# SheetMain.net
KiCad netlist of a schematic drawn in Altium Designer
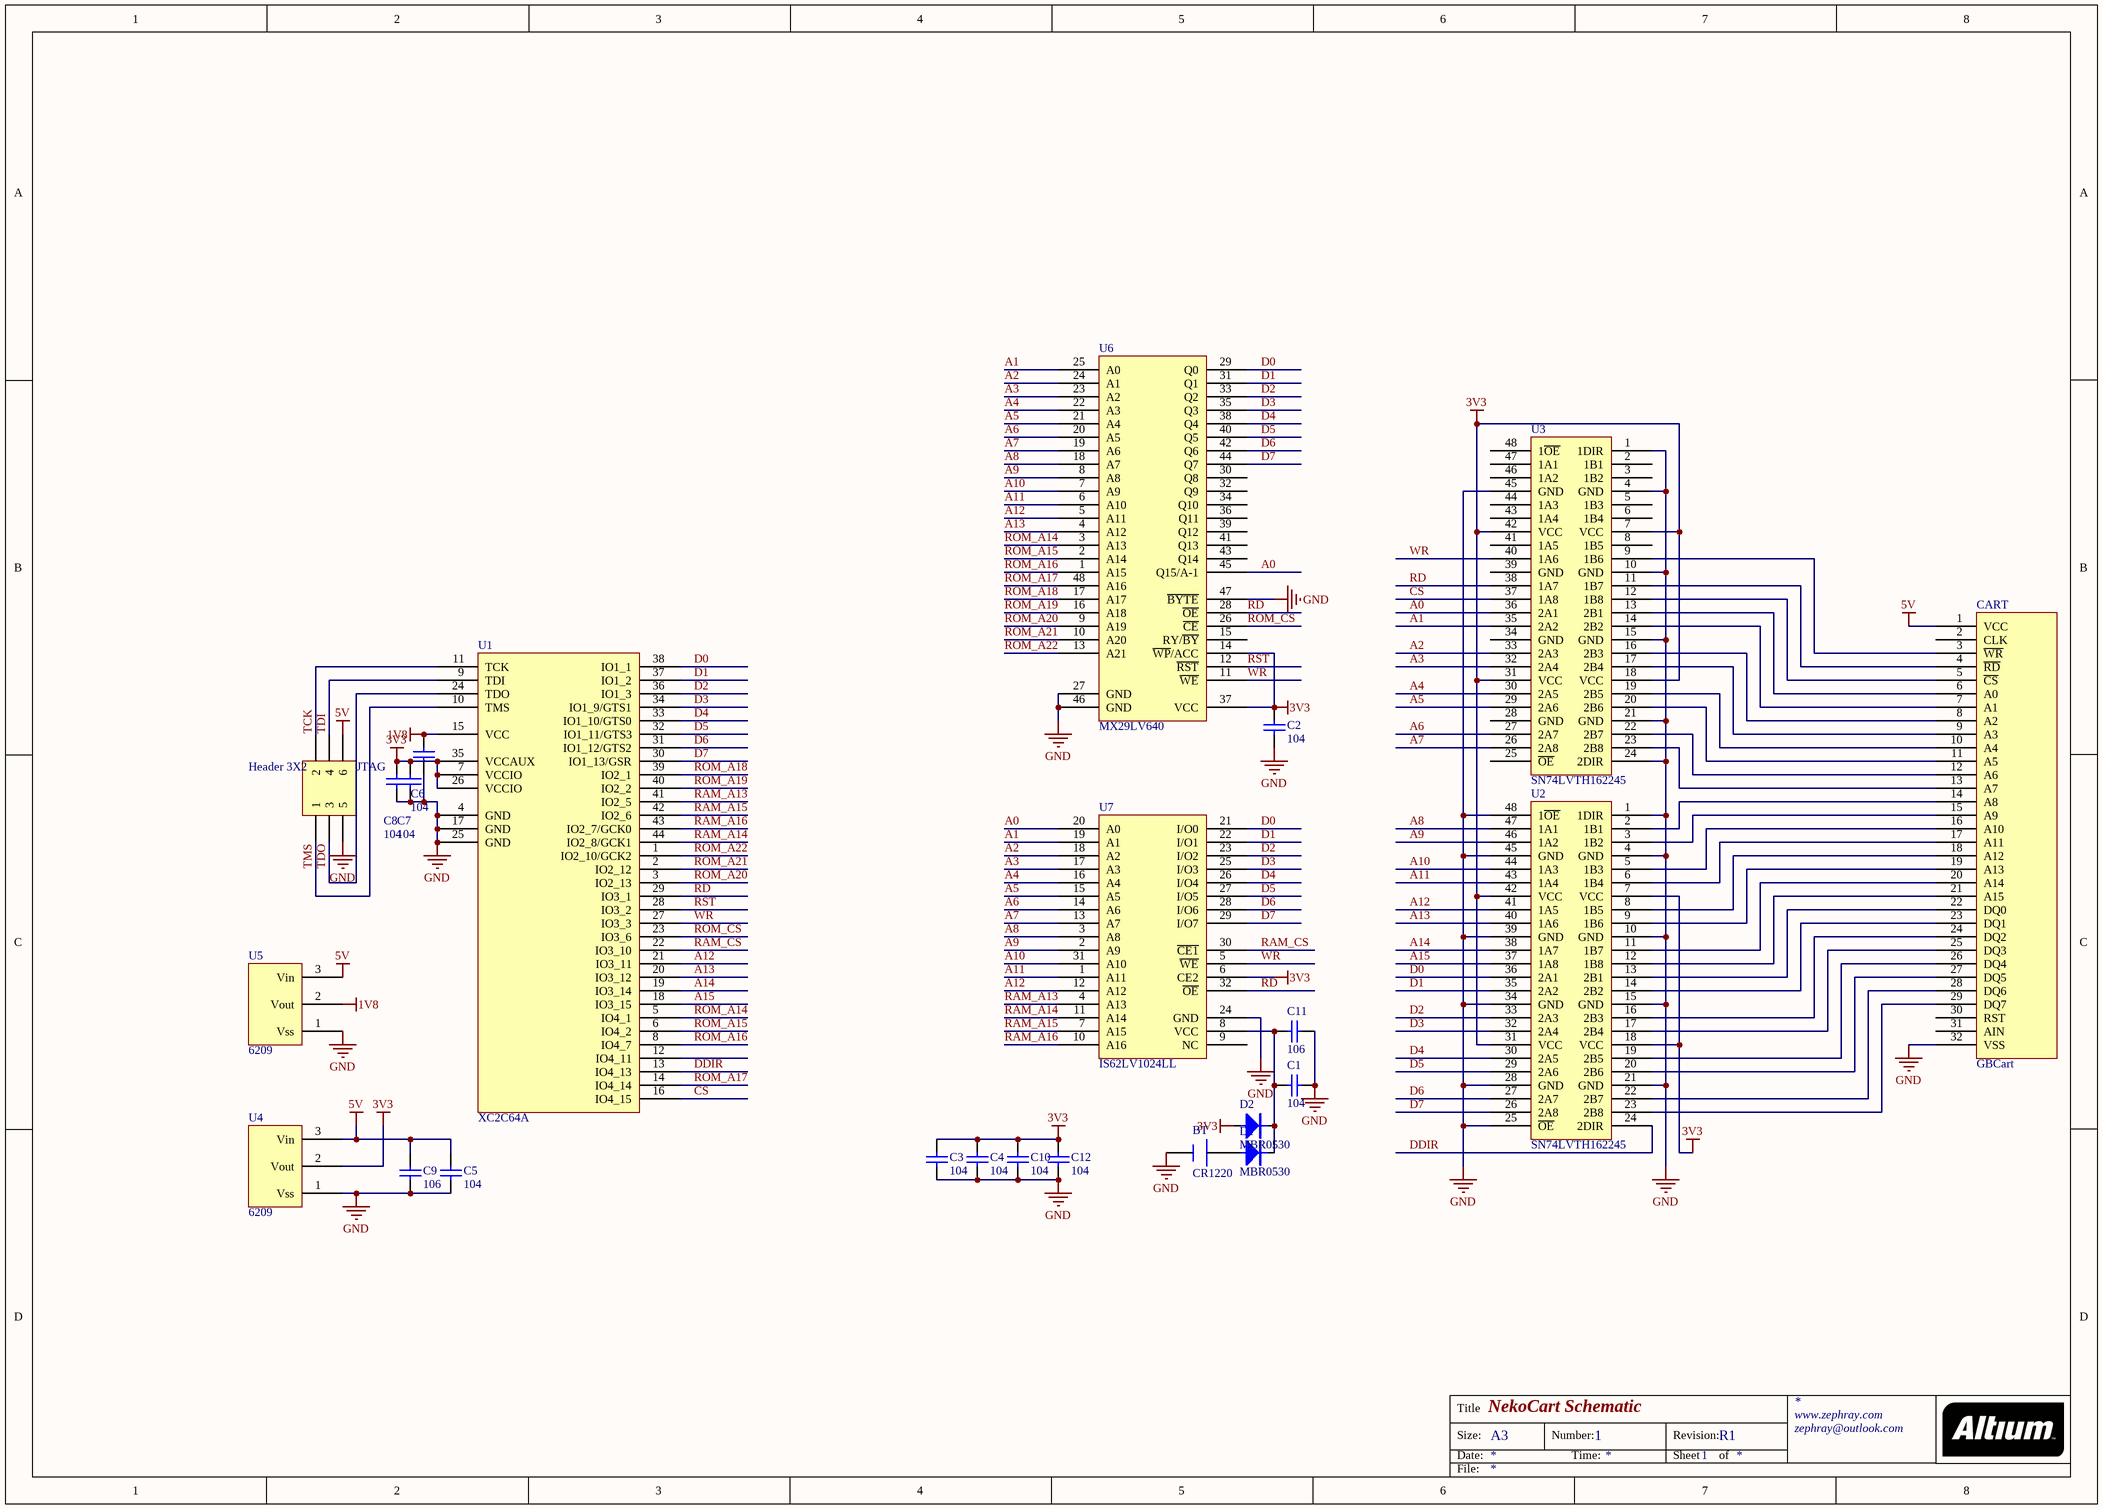
[diagram p0: SheetMain.SchDoc]

(export (version "E")
  (design (tool "Eeschema 10.0.6"))
  (components
    (comp (ref "BT")
      (value "CR1220")
      (footprint "CR1220")
      (fields (field (name "PUBLISHER") "Altium Limited"))
      (libsource (lib "Schlib1") (part "CR1220"))
    )
    (comp (ref "C1")
      (value "104")
      (footprint "1608[0603]")
      (description "Capacitor (Semiconductor SIM Model)")
      (fields (field (name "PUBLISHER") "Altium Limited"))
      (libsource (lib "Miscellaneous Devices") (part "Cap Semi"))
    )
    (comp (ref "C2")
      (value "104")
      (footprint "1608[0603]")
      (description "Capacitor (Semiconductor SIM Model)")
      (fields (field (name "PUBLISHER") "Altium Limited"))
      (libsource (lib "Miscellaneous Devices") (part "Cap Semi"))
    )
    (comp (ref "C3")
      (value "104")
      (footprint "1608[0603]")
      (description "Capacitor (Semiconductor SIM Model)")
      (fields (field (name "PUBLISHER") "Altium Limited"))
      (libsource (lib "Miscellaneous Devices") (part "Cap Semi"))
    )
    (comp (ref "C4")
      (value "104")
      (footprint "1608[0603]")
      (description "Capacitor (Semiconductor SIM Model)")
      (fields (field (name "PUBLISHER") "Altium Limited"))
      (libsource (lib "Miscellaneous Devices") (part "Cap Semi"))
    )
    (comp (ref "C5")
      (value "104")
      (footprint "1608[0603]")
      (description "Capacitor (Semiconductor SIM Model)")
      (fields (field (name "PUBLISHER") "Altium Limited"))
      (libsource (lib "Miscellaneous Devices") (part "Cap Semi"))
    )
    (comp (ref "C6")
      (value "104")
      (footprint "1608[0603]")
      (description "Capacitor (Semiconductor SIM Model)")
      (fields (field (name "PUBLISHER") "Altium Limited"))
      (libsource (lib "Miscellaneous Devices") (part "Cap Semi"))
    )
    (comp (ref "C7")
      (value "104")
      (footprint "1608[0603]")
      (description "Capacitor (Semiconductor SIM Model)")
      (fields (field (name "PUBLISHER") "Altium Limited"))
      (libsource (lib "Miscellaneous Devices") (part "Cap Semi"))
    )
    (comp (ref "C8")
      (value "104")
      (footprint "1608[0603]")
      (description "Capacitor (Semiconductor SIM Model)")
      (fields (field (name "PUBLISHER") "Altium Limited"))
      (libsource (lib "Miscellaneous Devices") (part "Cap Semi"))
    )
    (comp (ref "C9")
      (value "106")
      (footprint "C0805")
      (description "Capacitor (Semiconductor SIM Model)")
      (fields (field (name "PUBLISHER") "Altium Limited"))
      (libsource (lib "Miscellaneous Devices") (part "Cap Semi"))
    )
    (comp (ref "C10")
      (value "104")
      (footprint "1608[0603]")
      (description "Capacitor (Semiconductor SIM Model)")
      (fields (field (name "PUBLISHER") "Altium Limited"))
      (libsource (lib "Miscellaneous Devices") (part "Cap Semi"))
    )
    (comp (ref "C11")
      (value "106")
      (footprint "C0805")
      (description "Capacitor (Semiconductor SIM Model)")
      (fields (field (name "PUBLISHER") "Altium Limited"))
      (libsource (lib "Miscellaneous Devices") (part "Cap Semi"))
    )
    (comp (ref "C12")
      (value "104")
      (footprint "1608[0603]")
      (description "Capacitor (Semiconductor SIM Model)")
      (fields (field (name "PUBLISHER") "Altium Limited"))
      (libsource (lib "Miscellaneous Devices") (part "Cap Semi"))
    )
    (comp (ref "CART") (value "GBCart") (footprint "GB_CART") (libsource (lib "Schlib1") (part "GBCart")))
    (comp (ref "D1") (value "MBR0530") (footprint "0805D") (libsource (lib "Schlib1") (part "1N4148")))
    (comp (ref "D2") (value "MBR0530") (footprint "0805D") (libsource (lib "Schlib1") (part "1N4148")))
    (comp (ref "JTAG")
      (value "Header 3X2")
      (footprint "HDR2X3")
      (description "Header, 3-Pin, Dual row")
      (fields (field (name "PUBLISHER") "Altium Limited"))
      (libsource (lib "Miscellaneous Connectors") (part "Header 3X2"))
    )
    (comp (ref "U1") (value "XC2C64A") (footprint "44A_L") (libsource (lib "Schlib1") (part "XC2C64A")))
    (comp (ref "U2")
      (value "SN74LVTH162245")
      (footprint "TSOP48")
      (libsource (lib "Schlib1") (part "SN74LVTH162245"))
    )
    (comp (ref "U3")
      (value "SN74LVTH162245")
      (footprint "TSOP48")
      (libsource (lib "Schlib1") (part "SN74LVTH162245"))
    )
    (comp (ref "U4") (value "6209") (footprint "SOT-23") (libsource (lib "Schlib1") (part "6209")))
    (comp (ref "U5") (value "6209") (footprint "SOT-23") (libsource (lib "Schlib1") (part "6209")))
    (comp (ref "U6") (value "MX29LV640") (footprint "TSOP48L") (libsource (lib "Schlib1") (part "MX29LV640")))
    (comp (ref "U7")
      (value "IS62LV1024LL")
      (footprint "TSOP32")
      (libsource (lib "Schlib1") (part "IS62LV1024LL"))
    )
  )
  (nets
    (net (code "1") (name "/A0") (class "Default")
      (node (ref "U3") (pin "36") (pinfunction "2A1_36") (pintype "passive"))
      (node (ref "U6") (pin "45") (pinfunction "Q15/A-1_45") (pintype "passive"))
      (node (ref "U7") (pin "20") (pinfunction "A0_20") (pintype "passive"))
    )
    (net (code "2") (name "/A1") (class "Default")
      (node (ref "U3") (pin "35") (pinfunction "2A2_35") (pintype "passive"))
      (node (ref "U6") (pin "25") (pinfunction "A0_25") (pintype "passive"))
      (node (ref "U7") (pin "19") (pinfunction "A1_19") (pintype "passive"))
    )
    (net (code "3") (name "/A2") (class "Default")
      (node (ref "U3") (pin "33") (pinfunction "2A3_33") (pintype "passive"))
      (node (ref "U6") (pin "24") (pinfunction "A1_24") (pintype "passive"))
      (node (ref "U7") (pin "18") (pinfunction "A2_18") (pintype "passive"))
    )
    (net (code "4") (name "/A3") (class "Default")
      (node (ref "U3") (pin "32") (pinfunction "2A4_32") (pintype "passive"))
      (node (ref "U6") (pin "23") (pinfunction "A2_23") (pintype "passive"))
      (node (ref "U7") (pin "17") (pinfunction "A3_17") (pintype "passive"))
    )
    (net (code "5") (name "/A4") (class "Default")
      (node (ref "U3") (pin "30") (pinfunction "2A5_30") (pintype "passive"))
      (node (ref "U6") (pin "22") (pinfunction "A3_22") (pintype "passive"))
      (node (ref "U7") (pin "16") (pinfunction "A4_16") (pintype "passive"))
    )
    (net (code "6") (name "/A5") (class "Default")
      (node (ref "U3") (pin "29") (pinfunction "2A6_29") (pintype "passive"))
      (node (ref "U6") (pin "21") (pinfunction "A4_21") (pintype "passive"))
      (node (ref "U7") (pin "15") (pinfunction "A5_15") (pintype "passive"))
    )
    (net (code "7") (name "/A6") (class "Default")
      (node (ref "U3") (pin "27") (pinfunction "2A7_27") (pintype "passive"))
      (node (ref "U6") (pin "20") (pinfunction "A5_20") (pintype "passive"))
      (node (ref "U7") (pin "14") (pinfunction "A6_14") (pintype "passive"))
    )
    (net (code "8") (name "/A7") (class "Default")
      (node (ref "U3") (pin "26") (pinfunction "2A8_26") (pintype "passive"))
      (node (ref "U6") (pin "19") (pinfunction "A6_19") (pintype "passive"))
      (node (ref "U7") (pin "13") (pinfunction "A7_13") (pintype "passive"))
    )
    (net (code "9") (name "/A8") (class "Default")
      (node (ref "U2") (pin "47") (pinfunction "1A1_47") (pintype "passive"))
      (node (ref "U6") (pin "18") (pinfunction "A7_18") (pintype "passive"))
      (node (ref "U7") (pin "3") (pinfunction "A8_3") (pintype "passive"))
    )
    (net (code "10") (name "/A9") (class "Default")
      (node (ref "U2") (pin "46") (pinfunction "1A2_46") (pintype "passive"))
      (node (ref "U6") (pin "8") (pinfunction "A8_8") (pintype "passive"))
      (node (ref "U7") (pin "2") (pinfunction "A9_2") (pintype "passive"))
    )
    (net (code "11") (name "/A10") (class "Default")
      (node (ref "U2") (pin "44") (pinfunction "1A3_44") (pintype "passive"))
      (node (ref "U6") (pin "7") (pinfunction "A9_7") (pintype "passive"))
      (node (ref "U7") (pin "31") (pinfunction "A10_31") (pintype "passive"))
    )
    (net (code "12") (name "/A11") (class "Default")
      (node (ref "U2") (pin "43") (pinfunction "1A4_43") (pintype "passive"))
      (node (ref "U6") (pin "6") (pinfunction "A10_6") (pintype "passive"))
      (node (ref "U7") (pin "1") (pinfunction "A11_1") (pintype "passive"))
    )
    (net (code "13") (name "/A12") (class "Default")
      (node (ref "U1") (pin "21") (pinfunction "IO3_11_21") (pintype "passive"))
      (node (ref "U2") (pin "41") (pinfunction "1A5_41") (pintype "passive"))
      (node (ref "U6") (pin "5") (pinfunction "A11_5") (pintype "passive"))
      (node (ref "U7") (pin "12") (pinfunction "A12_12") (pintype "passive"))
    )
    (net (code "14") (name "/A13") (class "Default")
      (node (ref "U1") (pin "20") (pinfunction "IO3_12_20") (pintype "passive"))
      (node (ref "U2") (pin "40") (pinfunction "1A6_40") (pintype "passive"))
      (node (ref "U6") (pin "4") (pinfunction "A12_4") (pintype "passive"))
    )
    (net (code "15") (name "/A14") (class "Default")
      (node (ref "U1") (pin "19") (pinfunction "IO3_14_19") (pintype "passive"))
      (node (ref "U2") (pin "38") (pinfunction "1A7_38") (pintype "passive"))
    )
    (net (code "16") (name "/A15") (class "Default")
      (node (ref "U1") (pin "18") (pinfunction "IO3_15_18") (pintype "passive"))
      (node (ref "U2") (pin "37") (pinfunction "1A8_37") (pintype "passive"))
    )
    (net (code "17") (name "/CS") (class "Default")
      (node (ref "U1") (pin "16") (pinfunction "IO4_15_16") (pintype "passive"))
      (node (ref "U3") (pin "37") (pinfunction "1A8_37") (pintype "passive"))
    )
    (net (code "18") (name "/D0") (class "Default")
      (node (ref "U1") (pin "38") (pinfunction "IO1_1_38") (pintype "passive"))
      (node (ref "U2") (pin "36") (pinfunction "2A1_36") (pintype "passive"))
      (node (ref "U6") (pin "29") (pinfunction "Q0_29") (pintype "passive"))
      (node (ref "U7") (pin "21") (pinfunction "I/O0_21") (pintype "passive"))
    )
    (net (code "19") (name "/D1") (class "Default")
      (node (ref "U1") (pin "37") (pinfunction "IO1_2_37") (pintype "passive"))
      (node (ref "U2") (pin "35") (pinfunction "2A2_35") (pintype "passive"))
      (node (ref "U6") (pin "31") (pinfunction "Q1_31") (pintype "passive"))
      (node (ref "U7") (pin "22") (pinfunction "I/O1_22") (pintype "passive"))
    )
    (net (code "20") (name "/D2") (class "Default")
      (node (ref "U1") (pin "36") (pinfunction "IO1_3_36") (pintype "passive"))
      (node (ref "U2") (pin "33") (pinfunction "2A3_33") (pintype "passive"))
      (node (ref "U6") (pin "33") (pinfunction "Q2_33") (pintype "passive"))
      (node (ref "U7") (pin "23") (pinfunction "I/O2_23") (pintype "passive"))
    )
    (net (code "21") (name "/D3") (class "Default")
      (node (ref "U1") (pin "34") (pinfunction "IO1_9/GTS1_34") (pintype "passive"))
      (node (ref "U2") (pin "32") (pinfunction "2A4_32") (pintype "passive"))
      (node (ref "U6") (pin "35") (pinfunction "Q3_35") (pintype "passive"))
      (node (ref "U7") (pin "25") (pinfunction "I/O3_25") (pintype "passive"))
    )
    (net (code "22") (name "/D4") (class "Default")
      (node (ref "U1") (pin "33") (pinfunction "IO1_10/GTS0_33") (pintype "passive"))
      (node (ref "U2") (pin "30") (pinfunction "2A5_30") (pintype "passive"))
      (node (ref "U6") (pin "38") (pinfunction "Q4_38") (pintype "passive"))
      (node (ref "U7") (pin "26") (pinfunction "I/O4_26") (pintype "passive"))
    )
    (net (code "23") (name "/D5") (class "Default")
      (node (ref "U1") (pin "32") (pinfunction "IO1_11/GTS3_32") (pintype "passive"))
      (node (ref "U2") (pin "29") (pinfunction "2A6_29") (pintype "passive"))
      (node (ref "U6") (pin "40") (pinfunction "Q5_40") (pintype "passive"))
      (node (ref "U7") (pin "27") (pinfunction "I/O5_27") (pintype "passive"))
    )
    (net (code "24") (name "/D6") (class "Default")
      (node (ref "U1") (pin "31") (pinfunction "IO1_12/GTS2_31") (pintype "passive"))
      (node (ref "U2") (pin "27") (pinfunction "2A7_27") (pintype "passive"))
      (node (ref "U6") (pin "42") (pinfunction "Q6_42") (pintype "passive"))
      (node (ref "U7") (pin "28") (pinfunction "I/O6_28") (pintype "passive"))
    )
    (net (code "25") (name "/D7") (class "Default")
      (node (ref "U1") (pin "30") (pinfunction "IO1_13/GSR_30") (pintype "passive"))
      (node (ref "U2") (pin "26") (pinfunction "2A8_26") (pintype "passive"))
      (node (ref "U6") (pin "44") (pinfunction "Q7_44") (pintype "passive"))
      (node (ref "U7") (pin "29") (pinfunction "I/O7_29") (pintype "passive"))
    )
    (net (code "26") (name "/DDIR") (class "Default")
      (node (ref "U1") (pin "13") (pinfunction "IO4_13_13") (pintype "passive"))
      (node (ref "U2") (pin "24") (pinfunction "2DIR_24") (pintype "passive"))
    )
    (net (code "27") (name "/RAM_A13") (class "Default")
      (node (ref "U1") (pin "41") (pinfunction "IO2_5_41") (pintype "passive"))
      (node (ref "U7") (pin "4") (pinfunction "A13_4") (pintype "passive"))
    )
    (net (code "28") (name "/RAM_A14") (class "Default")
      (node (ref "U1") (pin "44") (pinfunction "IO2_8/GCK1_44") (pintype "passive"))
      (node (ref "U7") (pin "11") (pinfunction "A14_11") (pintype "passive"))
    )
    (net (code "29") (name "/RAM_A15") (class "Default")
      (node (ref "U1") (pin "42") (pinfunction "IO2_6_42") (pintype "passive"))
      (node (ref "U7") (pin "7") (pinfunction "A15_7") (pintype "passive"))
    )
    (net (code "30") (name "/RAM_A16") (class "Default")
      (node (ref "U1") (pin "43") (pinfunction "IO2_7/GCK0_43") (pintype "passive"))
      (node (ref "U7") (pin "10") (pinfunction "A16_10") (pintype "passive"))
    )
    (net (code "31") (name "/RAM_CS") (class "Default")
      (node (ref "U1") (pin "22") (pinfunction "IO3_10_22") (pintype "passive"))
      (node (ref "U7") (pin "30") (pinfunction "~{CE1}_30") (pintype "passive"))
    )
    (net (code "32") (name "/RD") (class "Default")
      (node (ref "U1") (pin "29") (pinfunction "IO3_1_29") (pintype "passive"))
      (node (ref "U3") (pin "38") (pinfunction "1A7_38") (pintype "passive"))
      (node (ref "U6") (pin "28") (pinfunction "~{OE}_28") (pintype "passive"))
      (node (ref "U7") (pin "32") (pinfunction "~{OE}_32") (pintype "passive"))
    )
    (net (code "33") (name "/ROM_A14") (class "Default")
      (node (ref "U1") (pin "5") (pinfunction "IO4_1_5") (pintype "passive"))
      (node (ref "U6") (pin "3") (pinfunction "A13_3") (pintype "passive"))
    )
    (net (code "34") (name "/ROM_A15") (class "Default")
      (node (ref "U1") (pin "6") (pinfunction "IO4_2_6") (pintype "passive"))
      (node (ref "U6") (pin "2") (pinfunction "A14_2") (pintype "passive"))
    )
    (net (code "35") (name "/ROM_A16") (class "Default")
      (node (ref "U1") (pin "8") (pinfunction "IO4_7_8") (pintype "passive"))
      (node (ref "U6") (pin "1") (pinfunction "A15_1") (pintype "passive"))
    )
    (net (code "36") (name "/ROM_A17") (class "Default")
      (node (ref "U1") (pin "14") (pinfunction "IO4_14_14") (pintype "passive"))
      (node (ref "U6") (pin "48") (pinfunction "A16_48") (pintype "passive"))
    )
    (net (code "37") (name "/ROM_A18") (class "Default")
      (node (ref "U1") (pin "39") (pinfunction "IO2_1_39") (pintype "passive"))
      (node (ref "U6") (pin "17") (pinfunction "A17_17") (pintype "passive"))
    )
    (net (code "38") (name "/ROM_A19") (class "Default")
      (node (ref "U1") (pin "40") (pinfunction "IO2_2_40") (pintype "passive"))
      (node (ref "U6") (pin "16") (pinfunction "A18_16") (pintype "passive"))
    )
    (net (code "39") (name "/ROM_A20") (class "Default")
      (node (ref "U1") (pin "3") (pinfunction "IO2_13_3") (pintype "passive"))
      (node (ref "U6") (pin "9") (pinfunction "A19_9") (pintype "passive"))
    )
    (net (code "40") (name "/ROM_A21") (class "Default")
      (node (ref "U1") (pin "2") (pinfunction "IO2_12_2") (pintype "passive"))
      (node (ref "U6") (pin "10") (pinfunction "A20_10") (pintype "passive"))
    )
    (net (code "41") (name "/ROM_A22") (class "Default")
      (node (ref "U1") (pin "1") (pinfunction "IO2_10/GCK2_1") (pintype "passive"))
      (node (ref "U6") (pin "13") (pinfunction "A21_13") (pintype "passive"))
    )
    (net (code "42") (name "/ROM_CS") (class "Default")
      (node (ref "U1") (pin "23") (pinfunction "IO3_6_23") (pintype "passive"))
      (node (ref "U6") (pin "26") (pinfunction "~{CE}_26") (pintype "passive"))
    )
    (net (code "43") (name "/RST") (class "Default")
      (node (ref "U1") (pin "28") (pinfunction "IO3_2_28") (pintype "passive"))
      (node (ref "U6") (pin "12") (pinfunction "~{RST}_12") (pintype "passive"))
    )
    (net (code "44") (name "/TCK") (class "Default")
      (node (ref "JTAG") (pin "2") (pinfunction "2_2") (pintype "passive"))
      (node (ref "U1") (pin "11") (pinfunction "TCK_11") (pintype "passive"))
    )
    (net (code "45") (name "/TDI") (class "Default")
      (node (ref "JTAG") (pin "4") (pinfunction "4_4") (pintype "passive"))
      (node (ref "U1") (pin "9") (pinfunction "TDI_9") (pintype "passive"))
    )
    (net (code "46") (name "/TDO") (class "Default")
      (node (ref "JTAG") (pin "3") (pinfunction "3_3") (pintype "passive"))
      (node (ref "U1") (pin "24") (pinfunction "TDO_24") (pintype "passive"))
    )
    (net (code "47") (name "/TMS") (class "Default")
      (node (ref "JTAG") (pin "1") (pinfunction "1_1") (pintype "passive"))
      (node (ref "U1") (pin "10") (pinfunction "TMS_10") (pintype "passive"))
    )
    (net (code "48") (name "/WR") (class "Default")
      (node (ref "U1") (pin "27") (pinfunction "IO3_3_27") (pintype "passive"))
      (node (ref "U3") (pin "40") (pinfunction "1A6_40") (pintype "passive"))
      (node (ref "U6") (pin "11") (pinfunction "~{WE}_11") (pintype "passive"))
      (node (ref "U7") (pin "5") (pinfunction "~{WE}_5") (pintype "passive"))
    )
    (net (code "49") (name "1V8") (class "Default")
      (node (ref "C6") (pin "2") (pinfunction "2_2") (pintype "passive"))
      (node (ref "U1") (pin "15") (pinfunction "VCC_15") (pintype "passive"))
      (node (ref "U5") (pin "2") (pinfunction "Vout_2") (pintype "passive"))
    )
    (net (code "50") (name "3V3") (class "Default")
      (node (ref "C10") (pin "1") (pinfunction "1_1") (pintype "passive"))
      (node (ref "C12") (pin "2") (pinfunction "2_2") (pintype "passive"))
      (node (ref "C2") (pin "2") (pinfunction "2_2") (pintype "passive"))
      (node (ref "C3") (pin "2") (pinfunction "2_2") (pintype "passive"))
      (node (ref "C4") (pin "2") (pinfunction "2_2") (pintype "passive"))
      (node (ref "C7") (pin "2") (pinfunction "2_2") (pintype "passive"))
      (node (ref "C8") (pin "2") (pinfunction "2_2") (pintype "passive"))
      (node (ref "D2") (pin "A") (pinfunction "1_A") (pintype "passive"))
      (node (ref "U1") (pin "26") (pinfunction "VCCIO_26") (pintype "passive"))
      (node (ref "U1") (pin "35") (pinfunction "VCCAUX_35") (pintype "passive"))
      (node (ref "U1") (pin "7") (pinfunction "VCCIO_7") (pintype "passive"))
      (node (ref "U2") (pin "18") (pinfunction "VCC_18") (pintype "passive"))
      (node (ref "U2") (pin "31") (pinfunction "VCC_31") (pintype "passive"))
      (node (ref "U2") (pin "42") (pinfunction "VCC_42") (pintype "passive"))
      (node (ref "U2") (pin "7") (pinfunction "VCC_7") (pintype "passive"))
      (node (ref "U3") (pin "18") (pinfunction "VCC_18") (pintype "passive"))
      (node (ref "U3") (pin "31") (pinfunction "VCC_31") (pintype "passive"))
      (node (ref "U3") (pin "42") (pinfunction "VCC_42") (pintype "passive"))
      (node (ref "U3") (pin "7") (pinfunction "VCC_7") (pintype "passive"))
      (node (ref "U4") (pin "2") (pinfunction "Vout_2") (pintype "passive"))
      (node (ref "U6") (pin "14") (pinfunction "~{WP}/ACC_14") (pintype "passive"))
      (node (ref "U6") (pin "37") (pinfunction "VCC_37") (pintype "passive"))
      (node (ref "U7") (pin "6") (pinfunction "CE2_6") (pintype "passive"))
    )
    (net (code "51") (name "5V") (class "Default")
      (node (ref "C5") (pin "2") (pinfunction "2_2") (pintype "passive"))
      (node (ref "C9") (pin "2") (pinfunction "2_2") (pintype "passive"))
      (node (ref "CART") (pin "1") (pinfunction "VCC_1") (pintype "passive"))
      (node (ref "JTAG") (pin "6") (pinfunction "6_6") (pintype "passive"))
      (node (ref "U4") (pin "3") (pinfunction "Vin_3") (pintype "passive"))
      (node (ref "U5") (pin "3") (pinfunction "Vin_3") (pintype "passive"))
    )
    (net (code "52") (name "GND") (class "Default")
      (node (ref "BT") (pin "2") (pinfunction "-_2") (pintype "passive"))
      (node (ref "C1") (pin "1") (pinfunction "1_1") (pintype "passive"))
      (node (ref "C10") (pin "2") (pinfunction "2_2") (pintype "passive"))
      (node (ref "C11") (pin "1") (pinfunction "1_1") (pintype "passive"))
      (node (ref "C12") (pin "1") (pinfunction "1_1") (pintype "passive"))
      (node (ref "C2") (pin "1") (pinfunction "1_1") (pintype "passive"))
      (node (ref "C3") (pin "1") (pinfunction "1_1") (pintype "passive"))
      (node (ref "C4") (pin "1") (pinfunction "1_1") (pintype "passive"))
      (node (ref "C5") (pin "1") (pinfunction "1_1") (pintype "passive"))
      (node (ref "C6") (pin "1") (pinfunction "1_1") (pintype "passive"))
      (node (ref "C7") (pin "1") (pinfunction "1_1") (pintype "passive"))
      (node (ref "C8") (pin "1") (pinfunction "1_1") (pintype "passive"))
      (node (ref "C9") (pin "1") (pinfunction "1_1") (pintype "passive"))
      (node (ref "CART") (pin "32") (pinfunction "VSS_32") (pintype "passive"))
      (node (ref "JTAG") (pin "5") (pinfunction "5_5") (pintype "passive"))
      (node (ref "U1") (pin "17") (pinfunction "GND_17") (pintype "passive"))
      (node (ref "U1") (pin "25") (pinfunction "GND_25") (pintype "passive"))
      (node (ref "U1") (pin "4") (pinfunction "GND_4") (pintype "passive"))
      (node (ref "U2") (pin "1") (pinfunction "1DIR_1") (pintype "passive"))
      (node (ref "U2") (pin "10") (pinfunction "GND_10") (pintype "passive"))
      (node (ref "U2") (pin "15") (pinfunction "GND_15") (pintype "passive"))
      (node (ref "U2") (pin "21") (pinfunction "GND_21") (pintype "passive"))
      (node (ref "U2") (pin "25") (pinfunction "~{OE}_25") (pintype "passive"))
      (node (ref "U2") (pin "28") (pinfunction "GND_28") (pintype "passive"))
      (node (ref "U2") (pin "34") (pinfunction "GND_34") (pintype "passive"))
      (node (ref "U2") (pin "39") (pinfunction "GND_39") (pintype "passive"))
      (node (ref "U2") (pin "4") (pinfunction "GND_4") (pintype "passive"))
      (node (ref "U2") (pin "45") (pinfunction "GND_45") (pintype "passive"))
      (node (ref "U2") (pin "48") (pinfunction "1~{OE}_48") (pintype "passive"))
      (node (ref "U3") (pin "1") (pinfunction "1DIR_1") (pintype "passive"))
      (node (ref "U3") (pin "10") (pinfunction "GND_10") (pintype "passive"))
      (node (ref "U3") (pin "15") (pinfunction "GND_15") (pintype "passive"))
      (node (ref "U3") (pin "21") (pinfunction "GND_21") (pintype "passive"))
      (node (ref "U3") (pin "24") (pinfunction "2DIR_24") (pintype "passive"))
      (node (ref "U3") (pin "4") (pinfunction "GND_4") (pintype "passive"))
      (node (ref "U3") (pin "45") (pinfunction "GND_45") (pintype "passive"))
      (node (ref "U4") (pin "1") (pinfunction "Vss_1") (pintype "passive"))
      (node (ref "U5") (pin "1") (pinfunction "Vss_1") (pintype "passive"))
      (node (ref "U6") (pin "27") (pinfunction "GND_27") (pintype "passive"))
      (node (ref "U6") (pin "46") (pinfunction "GND_46") (pintype "passive"))
      (node (ref "U6") (pin "47") (pinfunction "~{BYTE}_47") (pintype "passive"))
      (node (ref "U7") (pin "24") (pinfunction "GND_24") (pintype "passive"))
    )
    (net (code "53") (name "Net-(BT-+)") (class "Default")
      (node (ref "BT") (pin "1") (pinfunction "+_1") (pintype "passive"))
      (node (ref "D1") (pin "A") (pinfunction "1_A") (pintype "passive"))
    )
    (net (code "54") (name "Net-(CART-A0)") (class "Default")
      (node (ref "CART") (pin "6") (pinfunction "A0_6") (pintype "passive"))
      (node (ref "U3") (pin "13") (pinfunction "2B1_13") (pintype "passive"))
    )
    (net (code "55") (name "Net-(CART-A1)") (class "Default")
      (node (ref "CART") (pin "7") (pinfunction "A1_7") (pintype "passive"))
      (node (ref "U3") (pin "14") (pinfunction "2B2_14") (pintype "passive"))
    )
    (net (code "56") (name "Net-(CART-A2)") (class "Default")
      (node (ref "CART") (pin "8") (pinfunction "A2_8") (pintype "passive"))
      (node (ref "U3") (pin "16") (pinfunction "2B3_16") (pintype "passive"))
    )
    (net (code "57") (name "Net-(CART-A3)") (class "Default")
      (node (ref "CART") (pin "9") (pinfunction "A3_9") (pintype "passive"))
      (node (ref "U3") (pin "17") (pinfunction "2B4_17") (pintype "passive"))
    )
    (net (code "58") (name "Net-(CART-A4)") (class "Default")
      (node (ref "CART") (pin "10") (pinfunction "A4_10") (pintype "passive"))
      (node (ref "U3") (pin "19") (pinfunction "2B5_19") (pintype "passive"))
    )
    (net (code "59") (name "Net-(CART-A5)") (class "Default")
      (node (ref "CART") (pin "11") (pinfunction "A5_11") (pintype "passive"))
      (node (ref "U3") (pin "20") (pinfunction "2B6_20") (pintype "passive"))
    )
    (net (code "60") (name "Net-(CART-A6)") (class "Default")
      (node (ref "CART") (pin "12") (pinfunction "A6_12") (pintype "passive"))
      (node (ref "U3") (pin "22") (pinfunction "2B7_22") (pintype "passive"))
    )
    (net (code "61") (name "Net-(CART-A7)") (class "Default")
      (node (ref "CART") (pin "13") (pinfunction "A7_13") (pintype "passive"))
      (node (ref "U3") (pin "23") (pinfunction "2B8_23") (pintype "passive"))
    )
    (net (code "62") (name "Net-(CART-A8)") (class "Default")
      (node (ref "CART") (pin "14") (pinfunction "A8_14") (pintype "passive"))
      (node (ref "U2") (pin "2") (pinfunction "1B1_2") (pintype "passive"))
    )
    (net (code "63") (name "Net-(CART-A9)") (class "Default")
      (node (ref "CART") (pin "15") (pinfunction "A9_15") (pintype "passive"))
      (node (ref "U2") (pin "3") (pinfunction "1B2_3") (pintype "passive"))
    )
    (net (code "64") (name "Net-(CART-A10)") (class "Default")
      (node (ref "CART") (pin "16") (pinfunction "A10_16") (pintype "passive"))
      (node (ref "U2") (pin "5") (pinfunction "1B3_5") (pintype "passive"))
    )
    (net (code "65") (name "Net-(CART-A11)") (class "Default")
      (node (ref "CART") (pin "17") (pinfunction "A11_17") (pintype "passive"))
      (node (ref "U2") (pin "6") (pinfunction "1B4_6") (pintype "passive"))
    )
    (net (code "66") (name "Net-(CART-A12)") (class "Default")
      (node (ref "CART") (pin "18") (pinfunction "A12_18") (pintype "passive"))
      (node (ref "U2") (pin "8") (pinfunction "1B5_8") (pintype "passive"))
    )
    (net (code "67") (name "Net-(CART-A13)") (class "Default")
      (node (ref "CART") (pin "19") (pinfunction "A13_19") (pintype "passive"))
      (node (ref "U2") (pin "9") (pinfunction "1B6_9") (pintype "passive"))
    )
    (net (code "68") (name "Net-(CART-A14)") (class "Default")
      (node (ref "CART") (pin "20") (pinfunction "A14_20") (pintype "passive"))
      (node (ref "U2") (pin "11") (pinfunction "1B7_11") (pintype "passive"))
    )
    (net (code "69") (name "Net-(CART-A15)") (class "Default")
      (node (ref "CART") (pin "21") (pinfunction "A15_21") (pintype "passive"))
      (node (ref "U2") (pin "12") (pinfunction "1B8_12") (pintype "passive"))
    )
    (net (code "70") (name "Net-(CART-DQ0)") (class "Default")
      (node (ref "CART") (pin "22") (pinfunction "DQ0_22") (pintype "passive"))
      (node (ref "U2") (pin "13") (pinfunction "2B1_13") (pintype "passive"))
    )
    (net (code "71") (name "Net-(CART-DQ1)") (class "Default")
      (node (ref "CART") (pin "23") (pinfunction "DQ1_23") (pintype "passive"))
      (node (ref "U2") (pin "14") (pinfunction "2B2_14") (pintype "passive"))
    )
    (net (code "72") (name "Net-(CART-DQ2)") (class "Default")
      (node (ref "CART") (pin "24") (pinfunction "DQ2_24") (pintype "passive"))
      (node (ref "U2") (pin "16") (pinfunction "2B3_16") (pintype "passive"))
    )
    (net (code "73") (name "Net-(CART-DQ3)") (class "Default")
      (node (ref "CART") (pin "25") (pinfunction "DQ3_25") (pintype "passive"))
      (node (ref "U2") (pin "17") (pinfunction "2B4_17") (pintype "passive"))
    )
    (net (code "74") (name "Net-(CART-DQ4)") (class "Default")
      (node (ref "CART") (pin "26") (pinfunction "DQ4_26") (pintype "passive"))
      (node (ref "U2") (pin "19") (pinfunction "2B5_19") (pintype "passive"))
    )
    (net (code "75") (name "Net-(CART-DQ5)") (class "Default")
      (node (ref "CART") (pin "27") (pinfunction "DQ5_27") (pintype "passive"))
      (node (ref "U2") (pin "20") (pinfunction "2B6_20") (pintype "passive"))
    )
    (net (code "76") (name "Net-(CART-DQ6)") (class "Default")
      (node (ref "CART") (pin "28") (pinfunction "DQ6_28") (pintype "passive"))
      (node (ref "U2") (pin "22") (pinfunction "2B7_22") (pintype "passive"))
    )
    (net (code "77") (name "Net-(CART-DQ7)") (class "Default")
      (node (ref "CART") (pin "29") (pinfunction "DQ7_29") (pintype "passive"))
      (node (ref "U2") (pin "23") (pinfunction "2B8_23") (pintype "passive"))
    )
    (net (code "78") (name "Net-(CART-~{CS})") (class "Default")
      (node (ref "CART") (pin "5") (pinfunction "~{CS}_5") (pintype "passive"))
      (node (ref "U3") (pin "12") (pinfunction "1B8_12") (pintype "passive"))
    )
    (net (code "79") (name "Net-(CART-~{RD})") (class "Default")
      (node (ref "CART") (pin "4") (pinfunction "~{RD}_4") (pintype "passive"))
      (node (ref "U3") (pin "11") (pinfunction "1B7_11") (pintype "passive"))
    )
    (net (code "80") (name "Net-(CART-~{WR})") (class "Default")
      (node (ref "CART") (pin "3") (pinfunction "~{WR}_3") (pintype "passive"))
      (node (ref "U3") (pin "9") (pinfunction "1B6_9") (pintype "passive"))
    )
    (net (code "81") (name "Net-(D1-2)") (class "Default")
      (node (ref "C1") (pin "2") (pinfunction "2_2") (pintype "passive"))
      (node (ref "C11") (pin "2") (pinfunction "2_2") (pintype "passive"))
      (node (ref "D1") (pin "K") (pinfunction "2_K") (pintype "passive"))
      (node (ref "D2") (pin "K") (pinfunction "2_K") (pintype "passive"))
      (node (ref "U7") (pin "8") (pinfunction "VCC_8") (pintype "passive"))
    )
    (net (code "82") (name "unconnected-(CART-AIN-Pad31)") (class "Default")
      (node (ref "CART") (pin "31") (pinfunction "AIN_31") (pintype "passive"))
    )
    (net (code "83") (name "unconnected-(CART-CLK-Pad2)") (class "Default")
      (node (ref "CART") (pin "2") (pinfunction "CLK_2") (pintype "passive"))
    )
    (net (code "84") (name "unconnected-(CART-RST-Pad30)") (class "Default")
      (node (ref "CART") (pin "30") (pinfunction "RST_30") (pintype "passive"))
    )
    (net (code "85") (name "unconnected-(U1-IO4_11-Pad12)") (class "Default")
      (node (ref "U1") (pin "12") (pinfunction "IO4_11_12") (pintype "passive"))
    )
    (net (code "86") (name "unconnected-(U3-1A1-Pad47)") (class "Default")
      (node (ref "U3") (pin "47") (pinfunction "1A1_47") (pintype "passive"))
    )
    (net (code "87") (name "unconnected-(U3-1A2-Pad46)") (class "Default")
      (node (ref "U3") (pin "46") (pinfunction "1A2_46") (pintype "passive"))
    )
    (net (code "88") (name "unconnected-(U3-1A3-Pad44)") (class "Default")
      (node (ref "U3") (pin "44") (pinfunction "1A3_44") (pintype "passive"))
    )
    (net (code "89") (name "unconnected-(U3-1A4-Pad43)") (class "Default")
      (node (ref "U3") (pin "43") (pinfunction "1A4_43") (pintype "passive"))
    )
    (net (code "90") (name "unconnected-(U3-1A5-Pad41)") (class "Default")
      (node (ref "U3") (pin "41") (pinfunction "1A5_41") (pintype "passive"))
    )
    (net (code "91") (name "unconnected-(U3-1B1-Pad2)") (class "Default")
      (node (ref "U3") (pin "2") (pinfunction "1B1_2") (pintype "passive"))
    )
    (net (code "92") (name "unconnected-(U3-1B2-Pad3)") (class "Default")
      (node (ref "U3") (pin "3") (pinfunction "1B2_3") (pintype "passive"))
    )
    (net (code "93") (name "unconnected-(U3-1B3-Pad5)") (class "Default")
      (node (ref "U3") (pin "5") (pinfunction "1B3_5") (pintype "passive"))
    )
    (net (code "94") (name "unconnected-(U3-1B4-Pad6)") (class "Default")
      (node (ref "U3") (pin "6") (pinfunction "1B4_6") (pintype "passive"))
    )
    (net (code "95") (name "unconnected-(U3-1B5-Pad8)") (class "Default")
      (node (ref "U3") (pin "8") (pinfunction "1B5_8") (pintype "passive"))
    )
    (net (code "96") (name "unconnected-(U3-1~{OE}-Pad48)") (class "Default")
      (node (ref "U3") (pin "48") (pinfunction "1~{OE}_48") (pintype "passive"))
    )
    (net (code "97") (name "unconnected-(U3-GND-Pad28)") (class "Default")
      (node (ref "U3") (pin "28") (pinfunction "GND_28") (pintype "passive"))
    )
    (net (code "98") (name "unconnected-(U3-GND-Pad34)") (class "Default")
      (node (ref "U3") (pin "34") (pinfunction "GND_34") (pintype "passive"))
    )
    (net (code "99") (name "unconnected-(U3-GND-Pad39)") (class "Default")
      (node (ref "U3") (pin "39") (pinfunction "GND_39") (pintype "passive"))
    )
    (net (code "100") (name "unconnected-(U3-~{OE}-Pad25)") (class "Default")
      (node (ref "U3") (pin "25") (pinfunction "~{OE}_25") (pintype "passive"))
    )
    (net (code "101") (name "unconnected-(U6-Q8-Pad30)") (class "Default")
      (node (ref "U6") (pin "30") (pinfunction "Q8_30") (pintype "passive"))
    )
    (net (code "102") (name "unconnected-(U6-Q9-Pad32)") (class "Default")
      (node (ref "U6") (pin "32") (pinfunction "Q9_32") (pintype "passive"))
    )
    (net (code "103") (name "unconnected-(U6-Q10-Pad34)") (class "Default")
      (node (ref "U6") (pin "34") (pinfunction "Q10_34") (pintype "passive"))
    )
    (net (code "104") (name "unconnected-(U6-Q11-Pad36)") (class "Default")
      (node (ref "U6") (pin "36") (pinfunction "Q11_36") (pintype "passive"))
    )
    (net (code "105") (name "unconnected-(U6-Q12-Pad39)") (class "Default")
      (node (ref "U6") (pin "39") (pinfunction "Q12_39") (pintype "passive"))
    )
    (net (code "106") (name "unconnected-(U6-Q13-Pad41)") (class "Default")
      (node (ref "U6") (pin "41") (pinfunction "Q13_41") (pintype "passive"))
    )
    (net (code "107") (name "unconnected-(U6-Q14-Pad43)") (class "Default")
      (node (ref "U6") (pin "43") (pinfunction "Q14_43") (pintype "passive"))
    )
    (net (code "108") (name "unconnected-(U6-RY{slash}~{BY}-Pad15)") (class "Default")
      (node (ref "U6") (pin "15") (pinfunction "RY/~{BY}_15") (pintype "passive"))
    )
    (net (code "109") (name "unconnected-(U7-NC-Pad9)") (class "Default")
      (node (ref "U7") (pin "9") (pinfunction "NC_9") (pintype "passive"))
    )
  )
)
